# ac_dc_converter.net
KiCad netlist of a schematic drawn in Altium Designer
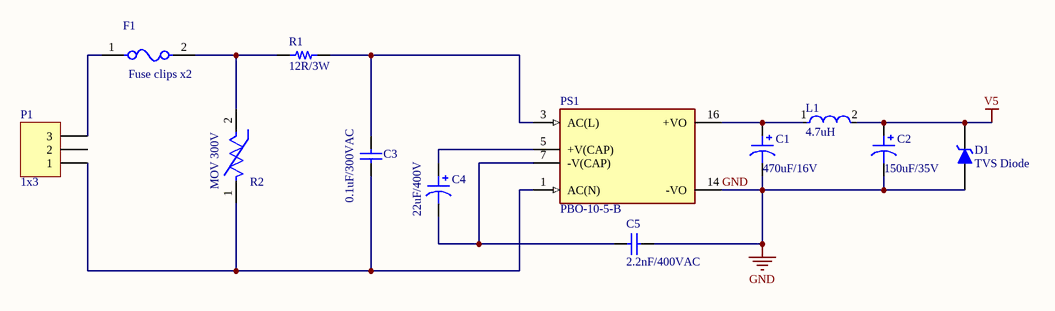
[diagram p0: ac_dc_converter.SchDoc]

(export (version "E")
  (design (tool "Eeschema 10.0.6"))
  (components
    (comp (ref "C1")
      (value "470uF/16V")
      (footprint "CAP TH ALPOLY D8.00mm S3.50mm H12.00mm")
      (description "SMT Polarised Capacitor")
      (fields (field (name "MF") "Panasonic") (field (name "MP") "ECA-1CM471B"))
      (libsource (lib "Capacitor") (part "Polarised Capacitor"))
    )
    (comp (ref "C2")
      (value "150uF/35V")
      (footprint "CAP TH ALPOLY D8.00mm S3.50mm H12.00mm")
      (description "SMT Polarised Capacitor")
      (fields (field (name "MF") "Wurth") (field (name "MP") "860040574005"))
      (libsource (lib "Capacitor") (part "Polarised Capacitor"))
    )
    (comp (ref "C3")
      (value "0.1uF/300VAC")
      (footprint "WCAP-FTX2_L13W7H13")
      (description "WCAP-FTX2 Film Capacitor, THT, L13W7H13")
      (fields (field (name "MF") "Wurth") (field (name "MP") "890324023023"))
      (libsource (lib "Capacitor") (part "Safety Capacitor"))
    )
    (comp (ref "C4")
      (value "22uF/400V")
      (footprint "CAP AL TH D16 L7.5 H20")
      (description "SMT Polarised Capacitor")
      (fields (field (name "MF") "Nichicon") (field (name "MP") "UCA2G220MHD6"))
      (libsource (lib "Capacitor") (part "Polarised Capacitor"))
    )
    (comp (ref "C5")
      (value "2.2nF/400VAC")
      (footprint "CAP TH SAFTY D7.00MM S7.50MM H11.00MM")
      (description "WCAP-FTX2 Film Capacitor, THT, L13W7H13")
      (fields (field (name "MF") "KEMET") (field (name "MP") "C907U222MYVDBA7317"))
      (libsource (lib "Capacitor") (part "Safety Capacitor"))
    )
    (comp (ref "D1")
      (value "TVS Diode")
      (footprint "Vishay_SMBJ7.0A")
      (fields (field (name "MF") "Vishay") (field (name "MP") "SMBJ7.0A-E3/52"))
      (libsource (lib "Diode") (part "TVS Diode 1ch uni"))
    )
    (comp (ref "F1")
      (value "Fuse clips x2")
      (footprint "5mm x 20mm fuse block")
      (description "FUSE BLOCK CART 250V 6.3A PCB 5mm x 20mm")
      (fields (field (name "MP") "3512") (field (name "VOLTAGE") "250V"))
      (libsource (lib "ProtectionDevice") (part "fuse block"))
    )
    (comp (ref "L1")
      (value "4.7uH")
      (footprint "IND RADIAL D8.70MM S5.00MM H12.50MM")
      (description "Fixed Inductors 2.2uH 20% High Temp AEC-Q200")
      (fields (field (name "MF") "Bourns") (field (name "MP") "RLB0913-4R7K"))
      (libsource (lib "Inductor") (part "Inductor_sm"))
    )
    (comp (ref "P1")
      (value "1x3")
      (footprint "Molex_NanoFit_1x3")
      (description "Header, 3-Pin, Right Angle")
      (fields
        (field (name "MF") "Molex")
        (field (name "MP") "105313-2103")
        (field (name "PUBLISHER") "Altium Limited")
      )
      (libsource (lib "Connector") (part "Header 3H"))
    )
    (comp (ref "PS1")
      (value "PBO-10-5-B")
      (footprint "CONV_PBO-10-5-B")
      (description "AC/DC Power Modules 5 Vdc, 2 A, 10 W")
      (fields (field (name "MF") "CUI Inc."))
      (libsource (lib "PowerBlock") (part "PBO-10-5-B"))
    )
    (comp (ref "R1")
      (value "12R/3W")
      (footprint "R2W_AX_VER")
      (description "THT Resistor")
      (fields (field (name "MF") "Yageo") (field (name "MP") "RSF3WSJT-73-12R"))
      (libsource (lib "Resistor") (part "Resistor"))
    )
    (comp (ref "R2")
      (value "MOV 300V")
      (footprint "EPCOS_0_0")
      (fields (field (name "MF") "TDK") (field (name "MP") "B72214S0301K101"))
      (libsource (lib "ProtectionDevice") (part "varistors"))
    )
  )
  (nets
    (net (code "1") (name "GND") (class "Default")
      (node (ref "C1") (pin "2") (pinfunction "2_2") (pintype "passive"))
      (node (ref "C2") (pin "2") (pinfunction "2_2") (pintype "passive"))
      (node (ref "C5") (pin "2") (pinfunction "2_2") (pintype "passive"))
      (node (ref "D1") (pin "2") (pinfunction "A_2") (pintype "passive"))
      (node (ref "PS1") (pin "14") (pinfunction "-VO_14") (pintype "power_in"))
    )
    (net (code "2") (name "Net-(F1-Pad1)") (class "Default")
      (node (ref "F1") (pin "1") (pinfunction "1_1") (pintype "passive"))
      (node (ref "P1") (pin "3") (pinfunction "3_3") (pintype "passive"))
    )
    (net (code "3") (name "Net-(F1-Pad2)") (class "Default")
      (node (ref "F1") (pin "2") (pinfunction "2_2") (pintype "passive"))
      (node (ref "R1") (pin "1") (pinfunction "1_1") (pintype "passive"))
      (node (ref "R2") (pin "2") (pinfunction "2_2") (pintype "passive"))
    )
    (net (code "4") (name "Net-(PS1-+V(CAP))") (class "Default")
      (node (ref "C4") (pin "1") (pinfunction "1_1") (pintype "passive"))
      (node (ref "PS1") (pin "5") (pinfunction "+V(CAP)_5") (pintype "passive"))
    )
    (net (code "5") (name "Net-(PS1-+VO)") (class "Default")
      (node (ref "C1") (pin "1") (pinfunction "1_1") (pintype "passive"))
      (node (ref "L1") (pin "1") (pinfunction "1_1") (pintype "passive"))
      (node (ref "PS1") (pin "16") (pinfunction "+VO_16") (pintype "power_in"))
    )
    (net (code "6") (name "Net-(PS1--V(CAP))") (class "Default")
      (node (ref "C4") (pin "2") (pinfunction "2_2") (pintype "passive"))
      (node (ref "C5") (pin "1") (pinfunction "1_1") (pintype "passive"))
      (node (ref "PS1") (pin "7") (pinfunction "-V(CAP)_7") (pintype "passive"))
    )
    (net (code "7") (name "Net-(PS1-AC(L))") (class "Default")
      (node (ref "C3") (pin "2") (pinfunction "2_2") (pintype "passive"))
      (node (ref "PS1") (pin "3") (pinfunction "AC(L)_3") (pintype "input"))
      (node (ref "R1") (pin "2") (pinfunction "2_2") (pintype "passive"))
    )
    (net (code "8") (name "Net-(PS1-AC(N))") (class "Default")
      (node (ref "C3") (pin "1") (pinfunction "1_1") (pintype "passive"))
      (node (ref "P1") (pin "1") (pinfunction "1_1") (pintype "passive"))
      (node (ref "PS1") (pin "1") (pinfunction "AC(N)_1") (pintype "input"))
      (node (ref "R2") (pin "1") (pinfunction "1_1") (pintype "passive"))
    )
    (net (code "9") (name "V5") (class "Default")
      (node (ref "C2") (pin "1") (pinfunction "1_1") (pintype "passive"))
      (node (ref "D1") (pin "1") (pinfunction "C_1") (pintype "passive"))
      (node (ref "L1") (pin "2") (pinfunction "2_2") (pintype "passive"))
    )
    (net (code "10") (name "unconnected-(P1-Pad2)") (class "Default")
      (node (ref "P1") (pin "2") (pinfunction "2_2") (pintype "passive"))
    )
  )
)
